# Battery_Sensor.net
KiCad netlist of a schematic drawn in Altium Designer
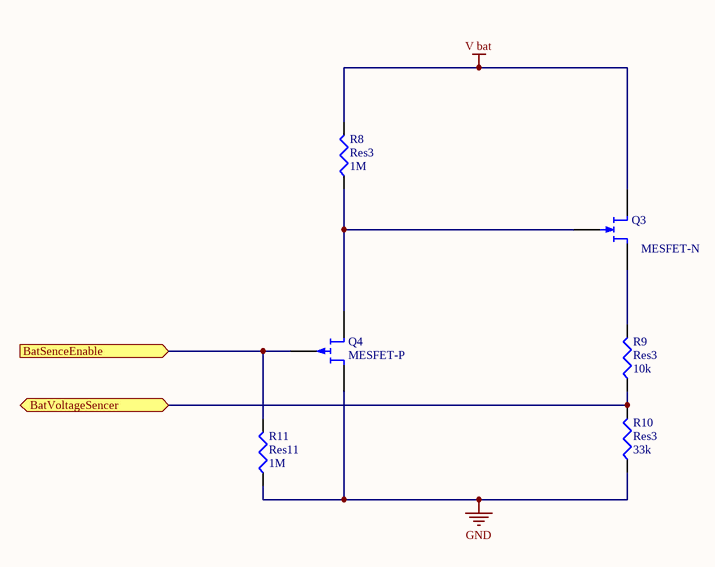
[diagram p0: Battery Sensor.SchDoc]

(export (version "E")
  (design (tool "Eeschema 10.0.6"))
  (components
    (comp (ref "Q3")
      (value "MESFET-N")
      (footprint "ONSC-SOT-323-3-419-04_V")
      (description "N-Channel MESFET")
      (fields (field (name "PUBLISHER") "Altium Limited"))
      (libsource (lib "Miscellaneous Devices") (part "MESFET-N"))
    )
    (comp (ref "Q4")
      (value "MESFET-P")
      (footprint "ONSC-SOT-323-3-419-04_V")
      (description "P-Channel MESFET")
      (fields (field (name "PUBLISHER") "Altium Limited"))
      (libsource (lib "Miscellaneous Devices") (part "MESFET-P"))
    )
    (comp (ref "R8")
      (value "Res3")
      (footprint "0402")
      (description "Resistor")
      (fields (field (name "ALTIUM_VALUE") "1M") (field (name "PUBLISHER") "Altium Limited"))
      (libsource (lib "Miscellaneous Devices") (part "Res3"))
    )
    (comp (ref "R9")
      (value "Res3")
      (footprint "0402")
      (description "Resistor")
      (fields (field (name "ALTIUM_VALUE") "10k") (field (name "PUBLISHER") "Altium Limited"))
      (libsource (lib "Miscellaneous Devices") (part "Res3"))
    )
    (comp (ref "R10")
      (value "Res3")
      (footprint "0402")
      (description "Resistor")
      (fields (field (name "ALTIUM_VALUE") "33k") (field (name "PUBLISHER") "Altium Limited"))
      (libsource (lib "Miscellaneous Devices") (part "Res3"))
    )
    (comp (ref "R11")
      (value "Res11")
      (footprint "0402")
      (description "Resistor")
      (fields (field (name "ALTIUM_VALUE") "1M") (field (name "PUBLISHER") "Altium Limited"))
      (libsource (lib "Miscellaneous Devices") (part "Res3"))
    )
  )
  (nets
    (net (code "1") (name "/BatSenceEnable") (class "Default")
      (node (ref "Q4") (pin "2") (pinfunction "G_2") (pintype "passive"))
      (node (ref "R11") (pin "2") (pinfunction "2_2") (pintype "passive"))
    )
    (net (code "2") (name "/BatVoltageSencer") (class "Default")
      (node (ref "R10") (pin "2") (pinfunction "2_2") (pintype "passive"))
      (node (ref "R9") (pin "1") (pinfunction "1_1") (pintype "passive"))
    )
    (net (code "3") (name "GND") (class "Default")
      (node (ref "Q4") (pin "1") (pinfunction "D_1") (pintype "passive"))
      (node (ref "R10") (pin "1") (pinfunction "1_1") (pintype "passive"))
      (node (ref "R11") (pin "1") (pinfunction "1_1") (pintype "passive"))
    )
    (net (code "4") (name "Net-(Q3-G)") (class "Default")
      (node (ref "Q3") (pin "2") (pinfunction "G_2") (pintype "passive"))
      (node (ref "Q4") (pin "3") (pinfunction "S_3") (pintype "passive"))
      (node (ref "R8") (pin "1") (pinfunction "1_1") (pintype "passive"))
    )
    (net (code "5") (name "Net-(Q3-S)") (class "Default")
      (node (ref "Q3") (pin "3") (pinfunction "S_3") (pintype "passive"))
      (node (ref "R9") (pin "2") (pinfunction "2_2") (pintype "passive"))
    )
    (net (code "6") (name "V bat") (class "Default")
      (node (ref "Q3") (pin "1") (pinfunction "D_1") (pintype "passive"))
      (node (ref "R8") (pin "2") (pinfunction "2_2") (pintype "passive"))
    )
  )
)
